# mcu_power.net
KiCad netlist of a schematic drawn in Altium Designer
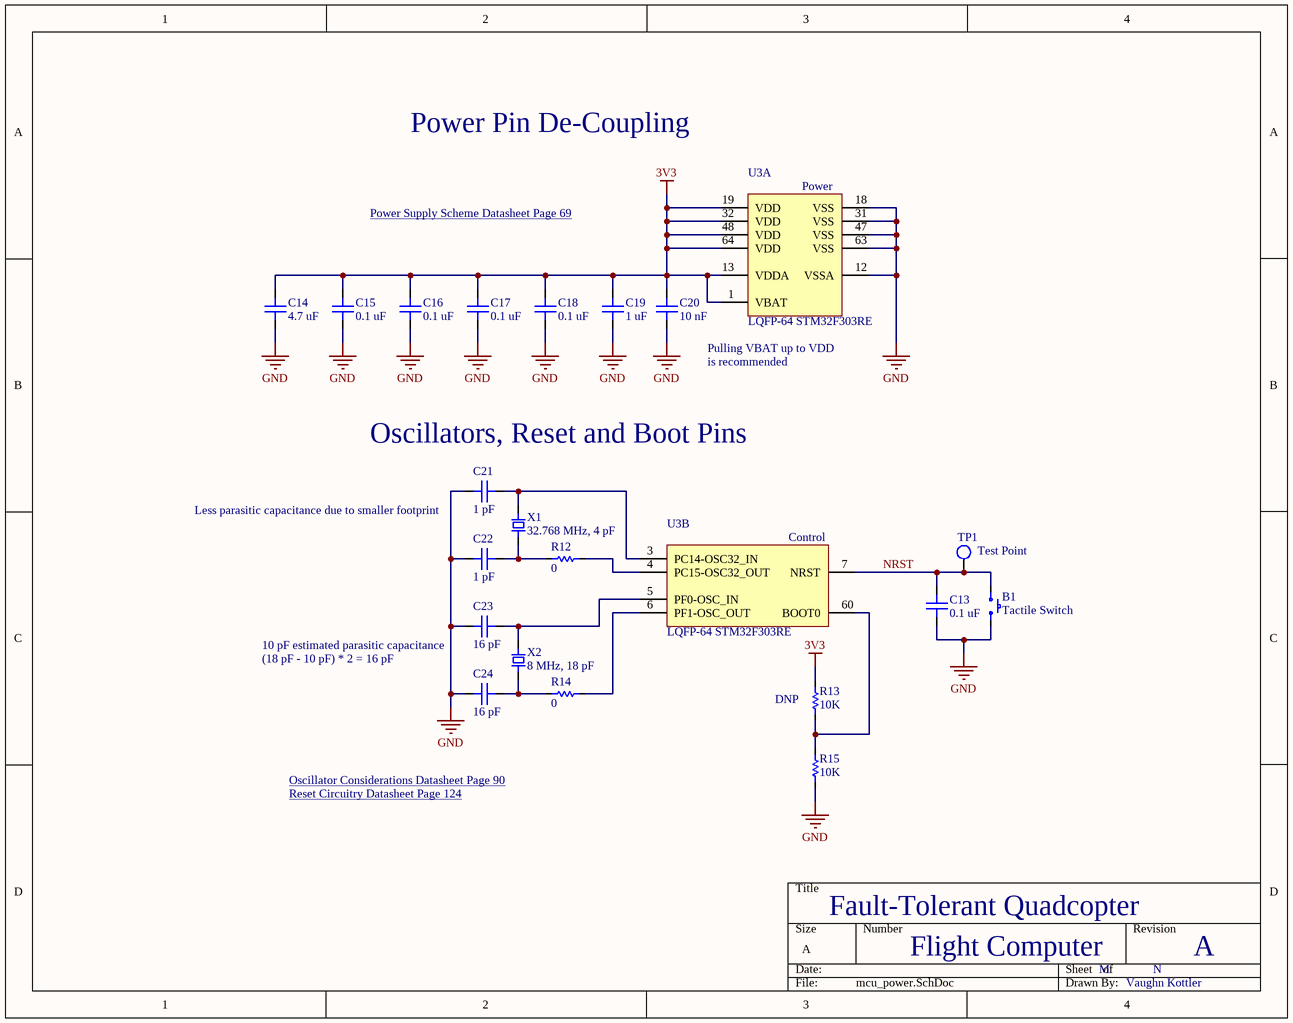
[diagram p0: mcu_power.SchDoc]

(export (version "E")
  (design (tool "Eeschema 10.0.6"))
  (components
    (comp (ref "B1")
      (value "Tactile Switch")
      (footprint "6mm Tactile Switch")
      (description "NO, MOM, 6mm")
      (libsource (lib "passive") (part "Tactile Switch"))
    )
    (comp (ref "C13")
      (value "0.1 uF")
      (footprint "CAP-CER-0805-SHORT")
      (description "10%, 0805")
      (libsource (lib "passive") (part "CAP-CER-0.1uF-25V"))
    )
    (comp (ref "C14")
      (value "4.7 uF")
      (footprint "CAP-CER-0805-TALL")
      (description "10%, 0805")
      (libsource (lib "passive") (part "CAP-CER-4.7uF-10V"))
    )
    (comp (ref "C15")
      (value "0.1 uF")
      (footprint "CAP-CER-0805-SHORT")
      (description "10%, 0805")
      (libsource (lib "passive") (part "CAP-CER-0.1uF-25V"))
    )
    (comp (ref "C16")
      (value "0.1 uF")
      (footprint "CAP-CER-0805-SHORT")
      (description "10%, 0805")
      (libsource (lib "passive") (part "CAP-CER-0.1uF-25V"))
    )
    (comp (ref "C17")
      (value "0.1 uF")
      (footprint "CAP-CER-0805-SHORT")
      (description "10%, 0805")
      (libsource (lib "passive") (part "CAP-CER-0.1uF-25V"))
    )
    (comp (ref "C18")
      (value "0.1 uF")
      (footprint "CAP-CER-0805-SHORT")
      (description "10%, 0805")
      (libsource (lib "passive") (part "CAP-CER-0.1uF-25V"))
    )
    (comp (ref "C19")
      (value "1 uF")
      (footprint "CAP-CER-0805-TALL")
      (description "10%, 0805")
      (libsource (lib "passive") (part "CAP-CER-1uF-10V"))
    )
    (comp (ref "C20")
      (value "10 nF")
      (footprint "CAP-CER-0805-SHORT")
      (description "10%, 0805")
      (libsource (lib "passive") (part "CAP-CER-10nF-50V"))
    )
    (comp (ref "C21")
      (value "1 pF")
      (footprint "CAP-CER-0805-SHORT")
      (description "±0.25pF, 0805")
      (libsource (lib "passive") (part "CAP-CER-1pF-50V"))
    )
    (comp (ref "C22")
      (value "1 pF")
      (footprint "CAP-CER-0805-SHORT")
      (description "±0.25pF, 0805")
      (libsource (lib "passive") (part "CAP-CER-1pF-50V"))
    )
    (comp (ref "C23")
      (value "16 pF")
      (footprint "CAP-CER-0805-SHORT")
      (description "±5%, 0805")
      (libsource (lib "passive") (part "CAP-CER-16pF-50V"))
    )
    (comp (ref "C24")
      (value "16 pF")
      (footprint "CAP-CER-0805-SHORT")
      (description "±5%, 0805")
      (libsource (lib "passive") (part "CAP-CER-16pF-50V"))
    )
    (comp (ref "R12")
      (value "0")
      (footprint "RES-0805")
      (description "0805")
      (libsource (lib "passive") (part "RES-0-1/8W"))
    )
    (comp (ref "R13")
      (value "10K")
      (footprint "RES-0805")
      (description "0805")
      (libsource (lib "passive") (part "RES-10K-1/8W"))
    )
    (comp (ref "R14")
      (value "0")
      (footprint "RES-0805")
      (description "0805")
      (libsource (lib "passive") (part "RES-0-1/8W"))
    )
    (comp (ref "R15")
      (value "10K")
      (footprint "RES-0805")
      (description "0805")
      (libsource (lib "passive") (part "RES-10K-1/8W"))
    )
    (comp (ref "TP1")
      (value "Test Point")
      (footprint "0603 Test Point")
      (description "0603")
      (libsource (lib "passive") (part "Test Point"))
    )
    (comp (ref "U3")
      (value "LQFP-64 STM32F303RE")
      (footprint "LQFP64")
      (description "ARM Cortex-M4 32-bit MCU+FPU")
      (libsource (lib "ic") (part "STM32F303RET6"))
    )
    (comp (ref "X1")
      (value "32.768 MHz, 4 pF")
      (footprint "XTAL-0805")
      (description "Crystal, 0805")
      (libsource (lib "passive") (part "XTAL-32.768kHz-4pF"))
    )
    (comp (ref "X2")
      (value "8 MHz, 18 pF")
      (footprint "HC-49")
      (description "Crystal, HC-49")
      (libsource (lib "passive") (part "XTAL-8MHz-18pF"))
    )
  )
  (nets
    (net (code "1") (name "/NRST") (class "Default")
      (node (ref "B1") (pin "1") (pinfunction "1_1") (pintype "passive"))
      (node (ref "C13") (pin "2") (pinfunction "2_2") (pintype "passive"))
      (node (ref "TP1") (pin "1") (pinfunction "1_1") (pintype "passive"))
      (node (ref "U3") (pin "7") (pinfunction "NRST_7") (pintype "passive"))
    )
    (net (code "2") (name "3V3") (class "Default")
      (node (ref "C14") (pin "2") (pinfunction "2_2") (pintype "passive"))
      (node (ref "C15") (pin "2") (pinfunction "2_2") (pintype "passive"))
      (node (ref "C16") (pin "2") (pinfunction "2_2") (pintype "passive"))
      (node (ref "C17") (pin "2") (pinfunction "2_2") (pintype "passive"))
      (node (ref "C18") (pin "2") (pinfunction "2_2") (pintype "passive"))
      (node (ref "C19") (pin "2") (pinfunction "2_2") (pintype "passive"))
      (node (ref "C20") (pin "2") (pinfunction "2_2") (pintype "passive"))
      (node (ref "R13") (pin "2") (pinfunction "2_2") (pintype "passive"))
      (node (ref "U3") (pin "1") (pinfunction "VBAT_1") (pintype "passive"))
      (node (ref "U3") (pin "13") (pinfunction "VDDA_13") (pintype "passive"))
      (node (ref "U3") (pin "19") (pinfunction "VDD_19") (pintype "passive"))
      (node (ref "U3") (pin "32") (pinfunction "VDD_32") (pintype "passive"))
      (node (ref "U3") (pin "48") (pinfunction "VDD_48") (pintype "passive"))
      (node (ref "U3") (pin "64") (pinfunction "VDD_64") (pintype "passive"))
    )
    (net (code "3") (name "GND") (class "Default")
      (node (ref "B1") (pin "2") (pinfunction "2_2") (pintype "passive"))
      (node (ref "C13") (pin "1") (pinfunction "1_1") (pintype "passive"))
      (node (ref "C14") (pin "1") (pinfunction "1_1") (pintype "passive"))
      (node (ref "C15") (pin "1") (pinfunction "1_1") (pintype "passive"))
      (node (ref "C16") (pin "1") (pinfunction "1_1") (pintype "passive"))
      (node (ref "C17") (pin "1") (pinfunction "1_1") (pintype "passive"))
      (node (ref "C18") (pin "1") (pinfunction "1_1") (pintype "passive"))
      (node (ref "C19") (pin "1") (pinfunction "1_1") (pintype "passive"))
      (node (ref "C20") (pin "1") (pinfunction "1_1") (pintype "passive"))
      (node (ref "C21") (pin "1") (pinfunction "1_1") (pintype "passive"))
      (node (ref "C22") (pin "1") (pinfunction "1_1") (pintype "passive"))
      (node (ref "C23") (pin "1") (pinfunction "1_1") (pintype "passive"))
      (node (ref "C24") (pin "1") (pinfunction "1_1") (pintype "passive"))
      (node (ref "R15") (pin "1") (pinfunction "1_1") (pintype "passive"))
      (node (ref "U3") (pin "12") (pinfunction "VSSA_12") (pintype "passive"))
      (node (ref "U3") (pin "18") (pinfunction "VSS_18") (pintype "passive"))
      (node (ref "U3") (pin "31") (pinfunction "VSS_31") (pintype "passive"))
      (node (ref "U3") (pin "47") (pinfunction "VSS_47") (pintype "passive"))
      (node (ref "U3") (pin "63") (pinfunction "VSS_63") (pintype "passive"))
    )
    (net (code "4") (name "Net-(C22-Pad2)") (class "Default")
      (node (ref "C22") (pin "2") (pinfunction "2_2") (pintype "passive"))
      (node (ref "R12") (pin "1") (pinfunction "1_1") (pintype "passive"))
      (node (ref "X1") (pin "1") (pinfunction "1_1") (pintype "passive"))
    )
    (net (code "5") (name "Net-(C24-Pad2)") (class "Default")
      (node (ref "C24") (pin "2") (pinfunction "2_2") (pintype "passive"))
      (node (ref "R14") (pin "1") (pinfunction "1_1") (pintype "passive"))
      (node (ref "X2") (pin "1") (pinfunction "1_1") (pintype "passive"))
    )
    (net (code "6") (name "Net-(U3B-BOOT0)") (class "Default")
      (node (ref "R13") (pin "1") (pinfunction "1_1") (pintype "passive"))
      (node (ref "R15") (pin "2") (pinfunction "2_2") (pintype "passive"))
      (node (ref "U3") (pin "60") (pinfunction "BOOT0_60") (pintype "passive"))
    )
    (net (code "7") (name "Net-(U3B-PC14-OSC32_IN)") (class "Default")
      (node (ref "C21") (pin "2") (pinfunction "2_2") (pintype "passive"))
      (node (ref "U3") (pin "3") (pinfunction "PC14-OSC32_IN_3") (pintype "passive"))
      (node (ref "X1") (pin "2") (pinfunction "2_2") (pintype "passive"))
    )
    (net (code "8") (name "Net-(U3B-PC15-OSC32_OUT)") (class "Default")
      (node (ref "R12") (pin "2") (pinfunction "2_2") (pintype "passive"))
      (node (ref "U3") (pin "4") (pinfunction "PC15-OSC32_OUT_4") (pintype "passive"))
    )
    (net (code "9") (name "Net-(U3B-PF0-OSC_IN)") (class "Default")
      (node (ref "C23") (pin "2") (pinfunction "2_2") (pintype "passive"))
      (node (ref "U3") (pin "5") (pinfunction "PF0-OSC_IN_5") (pintype "passive"))
      (node (ref "X2") (pin "2") (pinfunction "2_2") (pintype "passive"))
    )
    (net (code "10") (name "Net-(U3B-PF1-OSC_OUT)") (class "Default")
      (node (ref "R14") (pin "2") (pinfunction "2_2") (pintype "passive"))
      (node (ref "U3") (pin "6") (pinfunction "PF1-OSC_OUT_6") (pintype "passive"))
    )
  )
)
